# GateKeeper.net
KiCad netlist of a schematic drawn in EAGLE
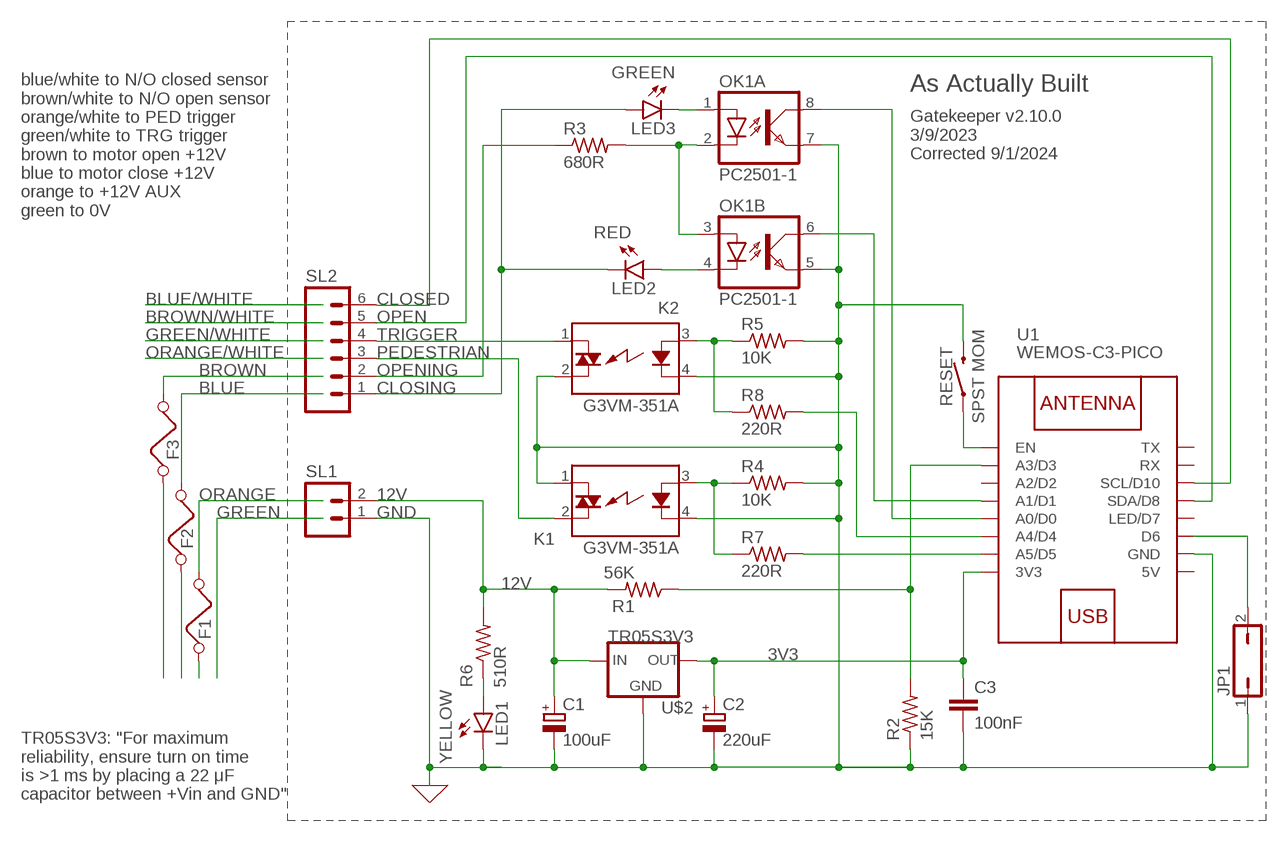
[diagram p0: schematic, sheet 1]

(export (version "E")
  (design (tool "Eeschema 10.0.6"))
  (components
    (comp (ref "C1")
      (value "100uF")
      (footprint "eagle-import:E2,5-5")
      (libsource (lib "eagle-import") (part "CPOL-EUE2.5-5"))
    )
    (comp (ref "C2")
      (value "220uF")
      (footprint "eagle-import:E2,5-5")
      (libsource (lib "eagle-import") (part "CPOL-EUE2.5-5"))
    )
    (comp (ref "C3")
      (value "100nF")
      (footprint "eagle-import:C2.5-2")
      (libsource (lib "eagle-import") (part "C2.5/2"))
    )
    (comp (ref "F1")
      (value "FUSE")
      (footprint "eagle-import:FUSE")
      (libsource (lib "eagle-import") (part "FUSE"))
    )
    (comp (ref "F2")
      (value "FUSE")
      (footprint "eagle-import:FUSE")
      (libsource (lib "eagle-import") (part "FUSE"))
    )
    (comp (ref "F3")
      (value "FUSE")
      (footprint "eagle-import:FUSE")
      (libsource (lib "eagle-import") (part "FUSE"))
    )
    (comp (ref "JP1")
      (value "JP1Q")
      (footprint "eagle-import:JP1")
      (libsource (lib "eagle-import") (part "JP1Q"))
    )
    (comp (ref "K1")
      (value "G3VM-351A")
      (footprint "eagle-import:S2XXEX")
      (libsource (lib "eagle-import") (part "S202SE1"))
    )
    (comp (ref "K2")
      (value "G3VM-351A")
      (footprint "eagle-import:S2XXEX")
      (libsource (lib "eagle-import") (part "S202SE1"))
    )
    (comp (ref "LED1")
      (value "YELLOW")
      (footprint "eagle-import:LED5MM")
      (libsource (lib "eagle-import") (part "LED5MM"))
    )
    (comp (ref "LED2")
      (value "RED")
      (footprint "eagle-import:LED5MM")
      (libsource (lib "eagle-import") (part "LED5MM"))
    )
    (comp (ref "LED3")
      (value "GREEN")
      (footprint "eagle-import:LED5MM")
      (libsource (lib "eagle-import") (part "LED5MM"))
    )
    (comp (ref "OK1")
      (value "PC2501-1")
      (footprint "eagle-import:DIL08")
      (libsource (lib "eagle-import") (part "PC827"))
    )
    (comp (ref "R1")
      (value "56K")
      (footprint "eagle-import:0207_10")
      (libsource (lib "eagle-import") (part "R-US_0207/10"))
    )
    (comp (ref "R2")
      (value "15K")
      (footprint "eagle-import:0207_10")
      (libsource (lib "eagle-import") (part "R-US_0207/10"))
    )
    (comp (ref "R3")
      (value "680R")
      (footprint "eagle-import:0207_10")
      (libsource (lib "eagle-import") (part "R-US_0207/10"))
    )
    (comp (ref "R4")
      (value "10K")
      (footprint "eagle-import:0207_10")
      (libsource (lib "eagle-import") (part "R-US_0207/10"))
    )
    (comp (ref "R5")
      (value "10K")
      (footprint "eagle-import:0207_10")
      (libsource (lib "eagle-import") (part "R-US_0207/10"))
    )
    (comp (ref "R6")
      (value "510R")
      (footprint "eagle-import:0207_10")
      (libsource (lib "eagle-import") (part "R-US_0207/10"))
    )
    (comp (ref "R7")
      (value "220R")
      (footprint "eagle-import:0207_10")
      (libsource (lib "eagle-import") (part "R-US_0207/10"))
    )
    (comp (ref "R8")
      (value "220R")
      (footprint "eagle-import:0207_10")
      (libsource (lib "eagle-import") (part "R-US_0207/10"))
    )
    (comp (ref "RESET")
      (value "SPST MOM")
      (footprint "eagle-import:TACTILE_SWITCH_PTH_6.0MM")
      (libsource (lib "eagle-import") (part "MOMENTARY-SWITCH-SPST-PTH-6.0MM"))
    )
    (comp (ref "SL1")
      (value "M02")
      (footprint "eagle-import:02P")
      (libsource (lib "eagle-import") (part "M02"))
    )
    (comp (ref "SL2")
      (value "M06")
      (footprint "eagle-import:06P")
      (libsource (lib "eagle-import") (part "M06"))
    )
    (comp (ref "U$2")
      (value "TR05S3V3")
      (footprint "eagle-import:78XXL")
      (libsource (lib "eagle-import") (part "V_REG_LD1117VXX"))
    )
    (comp (ref "U1")
      (value "WEMOS-C3-PICO")
      (footprint "eagle-import:WEMOS-C3-PICO")
      (libsource (lib "eagle-import") (part "WEMOS-C3-PICOWEMOS-C3-PICO"))
    )
  )
  (nets
    (net (code "1") (name "/3V3") (class "Default")
      (node (ref "C2") (pin "+") (pinfunction "+_+") (pintype "passive"))
      (node (ref "C3") (pin "1") (pinfunction "1_1") (pintype "passive"))
      (node (ref "U$2") (pin "GND") (pinfunction "OUT_GND") (pintype "passive"))
      (node (ref "U1") (pin "JP1.1") (pinfunction "3V3_JP1.1") (pintype "power_in"))
    )
    (net (code "2") (name "/5V") (class "Default")
      (node (ref "U1") (pin "JP1.2") (pinfunction "5V_JP1.2") (pintype "power_in"))
    )
    (net (code "3") (name "/12V") (class "Default")
      (node (ref "C1") (pin "+") (pinfunction "+_+") (pintype "passive"))
      (node (ref "R1") (pin "2") (pinfunction "2_2") (pintype "passive"))
      (node (ref "R6") (pin "2") (pinfunction "2_2") (pintype "passive"))
      (node (ref "SL1") (pin "2") (pinfunction "2_2") (pintype "passive"))
      (node (ref "U$2") (pin "OUT") (pinfunction "IN_OUT") (pintype "input"))
    )
    (net (code "4") (name "/BLUE") (class "Default")
      (node (ref "F2") (pin "2") (pinfunction "2_2") (pintype "passive"))
    )
    (net (code "6") (name "/BROWN") (class "Default")
      (node (ref "F3") (pin "2") (pinfunction "2_2") (pintype "passive"))
    )
    (net (code "8") (name "/CLOSED") (class "Default")
      (node (ref "SL2") (pin "6") (pinfunction "6_6") (pintype "passive"))
      (node (ref "U1") (pin "JP2.6") (pinfunction "SCL/D10_JP2.6") (pintype "bidirectional"))
    )
    (net (code "9") (name "/CLOSING") (class "Default")
      (node (ref "LED2") (pin "K") (pinfunction "C_K") (pintype "passive"))
      (node (ref "LED3") (pin "A") (pinfunction "A_A") (pintype "passive"))
      (node (ref "SL2") (pin "1") (pinfunction "1_1") (pintype "passive"))
    )
    (net (code "12") (name "/OPEN") (class "Default")
      (node (ref "SL2") (pin "5") (pinfunction "5_5") (pintype "passive"))
      (node (ref "U1") (pin "JP2.7") (pinfunction "SDA/D8_JP2.7") (pintype "bidirectional"))
    )
    (net (code "13") (name "/OPENING") (class "Default")
      (node (ref "R3") (pin "1") (pinfunction "1_1") (pintype "passive"))
      (node (ref "SL2") (pin "2") (pinfunction "2_2") (pintype "passive"))
    )
    (net (code "14") (name "/ORANGE") (class "Default")
      (node (ref "F1") (pin "2") (pinfunction "2_2") (pintype "passive"))
    )
    (net (code "16") (name "/PEDESTRIAN") (class "Default")
      (node (ref "K1") (pin "2") (pinfunction "DS2_2") (pintype "passive"))
      (node (ref "SL2") (pin "3") (pinfunction "3_3") (pintype "passive"))
    )
    (net (code "17") (name "/TRIGGER") (class "Default")
      (node (ref "K2") (pin "1") (pinfunction "DS1_1") (pintype "passive"))
      (node (ref "SL2") (pin "4") (pinfunction "4_4") (pintype "passive"))
    )
    (net (code "18") (name "GND") (class "Default")
      (node (ref "C1") (pin "-") (pinfunction "-_-") (pintype "passive"))
      (node (ref "C2") (pin "-") (pinfunction "-_-") (pintype "passive"))
      (node (ref "C3") (pin "2") (pinfunction "2_2") (pintype "passive"))
      (node (ref "JP1") (pin "1") (pinfunction "1_1") (pintype "passive"))
      (node (ref "K1") (pin "1") (pinfunction "DS1_1") (pintype "passive"))
      (node (ref "K1") (pin "4") (pinfunction "K_4") (pintype "passive"))
      (node (ref "K2") (pin "2") (pinfunction "DS2_2") (pintype "passive"))
      (node (ref "K2") (pin "4") (pinfunction "K_4") (pintype "passive"))
      (node (ref "LED1") (pin "K") (pinfunction "C_K") (pintype "passive"))
      (node (ref "OK1") (pin "5") (pinfunction "EMIT_5") (pintype "passive"))
      (node (ref "OK1") (pin "7") (pinfunction "EMIT_7") (pintype "passive"))
      (node (ref "R2") (pin "1") (pinfunction "1_1") (pintype "passive"))
      (node (ref "R4") (pin "2") (pinfunction "2_2") (pintype "passive"))
      (node (ref "R5") (pin "2") (pinfunction "2_2") (pintype "passive"))
      (node (ref "RESET") (pin "3") (pinfunction "2_3") (pintype "passive"))
      (node (ref "SL1") (pin "1") (pinfunction "1_1") (pintype "passive"))
      (node (ref "U$2") (pin "IN") (pinfunction "GND_IN") (pintype "input"))
      (node (ref "U1") (pin "JP2.2") (pinfunction "GND_JP2.2") (pintype "power_in"))
    )
    (net (code "19") (name "Net-(K1-A)") (class "Default")
      (node (ref "K1") (pin "3") (pinfunction "A_3") (pintype "passive"))
      (node (ref "R4") (pin "1") (pinfunction "1_1") (pintype "passive"))
      (node (ref "R7") (pin "1") (pinfunction "1_1") (pintype "passive"))
    )
    (net (code "20") (name "Net-(K2-A)") (class "Default")
      (node (ref "K2") (pin "3") (pinfunction "A_3") (pintype "passive"))
      (node (ref "R5") (pin "1") (pinfunction "1_1") (pintype "passive"))
      (node (ref "R8") (pin "1") (pinfunction "1_1") (pintype "passive"))
    )
    (net (code "21") (name "Net-(LED1-PadA)") (class "Default")
      (node (ref "LED1") (pin "A") (pinfunction "A_A") (pintype "passive"))
      (node (ref "R6") (pin "1") (pinfunction "1_1") (pintype "passive"))
    )
    (net (code "22") (name "Net-(LED3-C)") (class "Default")
      (node (ref "LED3") (pin "K") (pinfunction "C_K") (pintype "passive"))
      (node (ref "OK1") (pin "1") (pinfunction "A_1") (pintype "passive"))
    )
    (net (code "23") (name "Net-(OK1A-C)") (class "Default")
      (node (ref "OK1") (pin "2") (pinfunction "C_2") (pintype "passive"))
      (node (ref "OK1") (pin "3") (pinfunction "A_3") (pintype "passive"))
      (node (ref "R3") (pin "2") (pinfunction "2_2") (pintype "passive"))
    )
    (net (code "24") (name "Net-(OK1A-COL)") (class "Default")
      (node (ref "OK1") (pin "8") (pinfunction "COL_8") (pintype "passive"))
      (node (ref "U1") (pin "JP1.3") (pinfunction "A0/D0_JP1.3") (pintype "bidirectional"))
    )
    (net (code "25") (name "Net-(OK1B-C)") (class "Default")
      (node (ref "LED2") (pin "A") (pinfunction "A_A") (pintype "passive"))
      (node (ref "OK1") (pin "4") (pinfunction "C_4") (pintype "passive"))
    )
    (net (code "26") (name "Net-(OK1B-COL)") (class "Default")
      (node (ref "OK1") (pin "6") (pinfunction "COL_6") (pintype "passive"))
      (node (ref "U1") (pin "JP1.4") (pinfunction "A1/D1_JP1.4") (pintype "bidirectional"))
    )
    (net (code "27") (name "Net-(U1-A3{slash}D3)") (class "Default")
      (node (ref "R1") (pin "1") (pinfunction "1_1") (pintype "passive"))
      (node (ref "R2") (pin "2") (pinfunction "2_2") (pintype "passive"))
      (node (ref "U1") (pin "JP1.6") (pinfunction "A3/D3_JP1.6") (pintype "bidirectional"))
    )
    (net (code "28") (name "Net-(U1-A4{slash}D4)") (class "Default")
      (node (ref "R8") (pin "2") (pinfunction "2_2") (pintype "passive"))
      (node (ref "U1") (pin "JP1.7") (pinfunction "A4/D4_JP1.7") (pintype "bidirectional"))
    )
    (net (code "29") (name "Net-(U1-A5{slash}D5)") (class "Default")
      (node (ref "R7") (pin "2") (pinfunction "2_2") (pintype "passive"))
      (node (ref "U1") (pin "JP1.8") (pinfunction "A5/D5_JP1.8") (pintype "bidirectional"))
    )
    (net (code "30") (name "Net-(U1-D6)") (class "Default")
      (node (ref "JP1") (pin "2") (pinfunction "2_2") (pintype "passive"))
      (node (ref "U1") (pin "JP2.1") (pinfunction "D6_JP2.1") (pintype "bidirectional"))
    )
    (net (code "31") (name "Net-(U1-EN)") (class "Default")
      (node (ref "RESET") (pin "1") (pinfunction "1_1") (pintype "passive"))
      (node (ref "U1") (pin "JP2.4") (pinfunction "EN_JP2.4") (pintype "input"))
    )
    (net (code "32") (name "unconnected-(F1-Pad1)") (class "Default")
      (node (ref "F1") (pin "1") (pinfunction "1_1") (pintype "passive"))
    )
    (net (code "33") (name "unconnected-(F2-Pad1)") (class "Default")
      (node (ref "F2") (pin "1") (pinfunction "1_1") (pintype "passive"))
    )
    (net (code "34") (name "unconnected-(F3-Pad1)") (class "Default")
      (node (ref "F3") (pin "1") (pinfunction "1_1") (pintype "passive"))
    )
    (net (code "35") (name "unconnected-(U1-A2{slash}D2-PadJP1.5)") (class "Default")
      (node (ref "U1") (pin "JP1.5") (pinfunction "A2/D2_JP1.5") (pintype "bidirectional"))
    )
    (net (code "36") (name "unconnected-(U1-LED{slash}D7-PadJP2.3)") (class "Default")
      (node (ref "U1") (pin "JP2.3") (pinfunction "LED/D7_JP2.3") (pintype "bidirectional"))
    )
    (net (code "37") (name "unconnected-(U1-RX-PadJP2.5)") (class "Default")
      (node (ref "U1") (pin "JP2.5") (pinfunction "RX_JP2.5") (pintype "input"))
    )
    (net (code "38") (name "unconnected-(U1-TX-PadJP2.8)") (class "Default")
      (node (ref "U1") (pin "JP2.8") (pinfunction "TX_JP2.8") (pintype "output"))
    )
  )
)
